# 3_ADC_INPUT_BIAS.net
KiCad netlist of a schematic drawn in Altium Designer
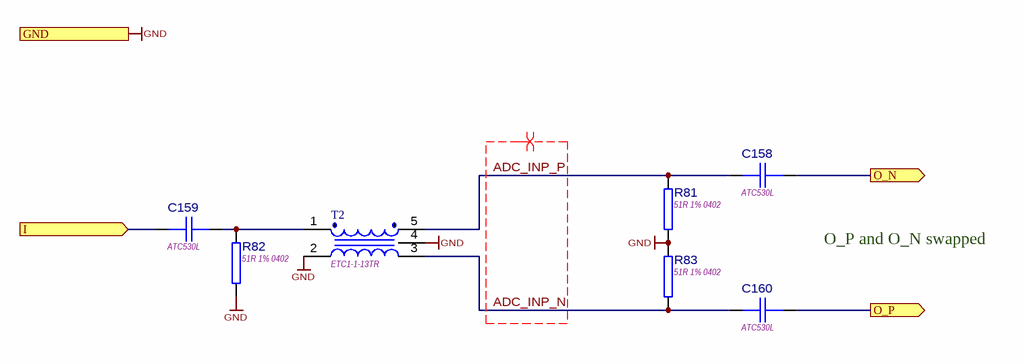
[diagram p0: [3] ADC_INPUT_BIAS.SchDoc]

(export (version "E")
  (design (tool "Eeschema 10.0.6"))
  (components
    (comp (ref "C158")
      (value "ATC530L")
      (footprint "CAPC1005X06L")
      (description "100n 16V ±15% 0402 (1005 metric) ATC530L104KT16T")
      (fields (field (name "TOLERANCE") "±15%"))
      (libsource (lib "Omnisys Vault") (part "CAP-2PIN"))
    )
    (comp (ref "C159")
      (value "ATC530L")
      (footprint "CAPC1005X06L")
      (description "100n 16V ±15% 0402 (1005 metric) ATC530L104KT16T")
      (fields (field (name "TOLERANCE") "±15%"))
      (libsource (lib "Omnisys Vault") (part "CAP-2PIN"))
    )
    (comp (ref "C160")
      (value "ATC530L")
      (footprint "CAPC1005X06L")
      (description "100n 16V ±15% 0402 (1005 metric) ATC530L104KT16T")
      (fields (field (name "TOLERANCE") "±15%"))
      (libsource (lib "Omnisys Vault") (part "CAP-2PIN"))
    )
    (comp (ref "R81")
      (value "51R 1% 0402")
      (footprint "RESC1005L")
      (description "Thick film Chip Resistor, 0402/1005")
      (fields (field (name "POWER") "100mW") (field (name "TOLERANCE") "1%"))
      (libsource (lib "Omnisys Vault") (part "RES-2PIN"))
    )
    (comp (ref "R82")
      (value "51R 1% 0402")
      (footprint "RESC1005L")
      (description "Thick film Chip Resistor, 0402/1005")
      (fields (field (name "POWER") "100mW") (field (name "TOLERANCE") "1%"))
      (libsource (lib "Omnisys Vault") (part "RES-2PIN"))
    )
    (comp (ref "R83")
      (value "51R 1% 0402")
      (footprint "RESC1005L")
      (description "Thick film Chip Resistor, 0402/1005")
      (fields (field (name "POWER") "100mW") (field (name "TOLERANCE") "1%"))
      (libsource (lib "Omnisys Vault") (part "RES-2PIN"))
    )
    (comp (ref "T2")
      (value "ETC1-1-13TR")
      (footprint "SOTFL50P160X73-3N")
      (description "Transformers Audio & Signal 4.5-3000MHz IL 2dB Impedance Ratio 1:1")
      (libsource (lib "Omnisys Vault") (part "ETC1-1-13TR"))
    )
  )
  (nets
    (net (code "1") (name "/ADC_INP_N") (class "Default")
      (node (ref "C160") (pin "2") (pinfunction "2_2") (pintype "passive"))
      (node (ref "R83") (pin "1") (pinfunction "1_1") (pintype "passive"))
      (node (ref "T2") (pin "3") (pinfunction "Secondary_3") (pintype "passive"))
    )
    (net (code "2") (name "/ADC_INP_P") (class "Default")
      (node (ref "C158") (pin "2") (pinfunction "2_2") (pintype "passive"))
      (node (ref "R81") (pin "2") (pinfunction "2_2") (pintype "passive"))
      (node (ref "T2") (pin "5") (pinfunction "Secondary_dot_5") (pintype "passive"))
    )
    (net (code "3") (name "/I") (class "Default")
      (node (ref "C159") (pin "2") (pinfunction "2_2") (pintype "passive"))
    )
    (net (code "4") (name "/O_N") (class "Default")
      (node (ref "C158") (pin "1") (pinfunction "1_1") (pintype "passive"))
    )
    (net (code "5") (name "/O_P") (class "Default")
      (node (ref "C160") (pin "1") (pinfunction "1_1") (pintype "passive"))
    )
    (net (code "6") (name "GND") (class "Default")
      (node (ref "R81") (pin "1") (pinfunction "1_1") (pintype "passive"))
      (node (ref "R82") (pin "2") (pinfunction "2_2") (pintype "passive"))
      (node (ref "R83") (pin "2") (pinfunction "2_2") (pintype "passive"))
      (node (ref "T2") (pin "2") (pinfunction "Primary_2") (pintype "passive"))
      (node (ref "T2") (pin "4") (pinfunction "NC_4") (pintype "passive"))
    )
    (net (code "7") (name "Net-(T2-Primary_dot)") (class "Default")
      (node (ref "C159") (pin "1") (pinfunction "1_1") (pintype "passive"))
      (node (ref "R82") (pin "1") (pinfunction "1_1") (pintype "passive"))
      (node (ref "T2") (pin "1") (pinfunction "Primary_dot_1") (pintype "passive"))
    )
  )
)
